# voltage-reference-5_0V.net
KiCad netlist of a schematic drawn in Altium Designer
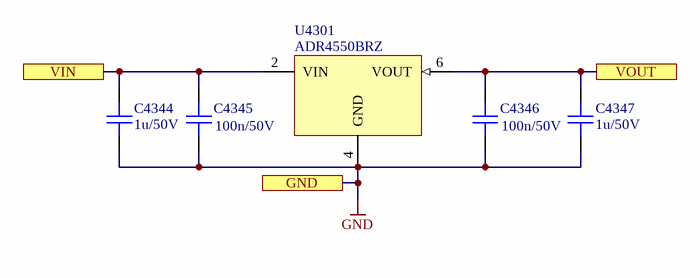
[diagram p0: voltage-reference-5.0V.SchDoc]

(export (version "E")
  (design (tool "Eeschema 10.0.6"))
  (components
    (comp (ref "C4344")
      (value "1u/50V")
      (footprint "CAPC1608X08N")
      (description "MLCC")
      (fields (field (name "PART NUMBER") "gen_C_ceramic_1u_50V_X7R_0603") (field (name "TOLERANCE") "± 10%"))
      (libsource (lib "OE750") (part "C"))
    )
    (comp (ref "C4345")
      (value "100n/50V")
      (footprint "CAPC1005X06N")
      (description "MLCC")
      (fields (field (name "PART NUMBER") "gen_C_ceramic_100n_50V_X7R_0402"))
      (libsource (lib "OE750") (part "C"))
    )
    (comp (ref "C4346")
      (value "100n/50V")
      (footprint "CAPC1005X06N")
      (description "MLCC")
      (fields (field (name "PART NUMBER") "gen_C_ceramic_100n_50V_X7R_0402"))
      (libsource (lib "OE750") (part "C"))
    )
    (comp (ref "C4347")
      (value "1u/50V")
      (footprint "CAPC1608X08N")
      (description "MLCC")
      (fields (field (name "PART NUMBER") "gen_C_ceramic_1u_50V_X7R_0603") (field (name "TOLERANCE") "± 10%"))
      (libsource (lib "OE750") (part "C"))
    )
    (comp (ref "U4301")
      (value "ADR4550BRZ")
      (footprint "SOIC127P600X175-8N")
      (description "Ultralow Noise, High Accuracy Voltage Reference")
      (fields (field (name "MANUFACTURER") "Analog Devices"))
      (libsource (lib "OE750") (part "ADR4525ARZ"))
    )
  )
  (nets
    (net (code "1") (name "/VIN") (class "Default")
      (node (ref "C4344") (pin "2") (pinfunction "2_2") (pintype "passive"))
      (node (ref "C4345") (pin "2") (pinfunction "2_2") (pintype "passive"))
      (node (ref "U4301") (pin "2") (pinfunction "VIN_2") (pintype "power_in"))
    )
    (net (code "2") (name "/VOUT") (class "Default")
      (node (ref "C4346") (pin "2") (pinfunction "2_2") (pintype "passive"))
      (node (ref "C4347") (pin "2") (pinfunction "2_2") (pintype "passive"))
      (node (ref "U4301") (pin "6") (pinfunction "VOUT_6") (pintype "input"))
    )
    (net (code "3") (name "GND") (class "Default")
      (node (ref "C4344") (pin "1") (pinfunction "1_1") (pintype "passive"))
      (node (ref "C4345") (pin "1") (pinfunction "1_1") (pintype "passive"))
      (node (ref "C4346") (pin "1") (pinfunction "1_1") (pintype "passive"))
      (node (ref "C4347") (pin "1") (pinfunction "1_1") (pintype "passive"))
      (node (ref "U4301") (pin "4") (pinfunction "GND_4") (pintype "power_in"))
    )
  )
)
